# BLE_Node.net
KiCad netlist of a schematic drawn in EAGLE
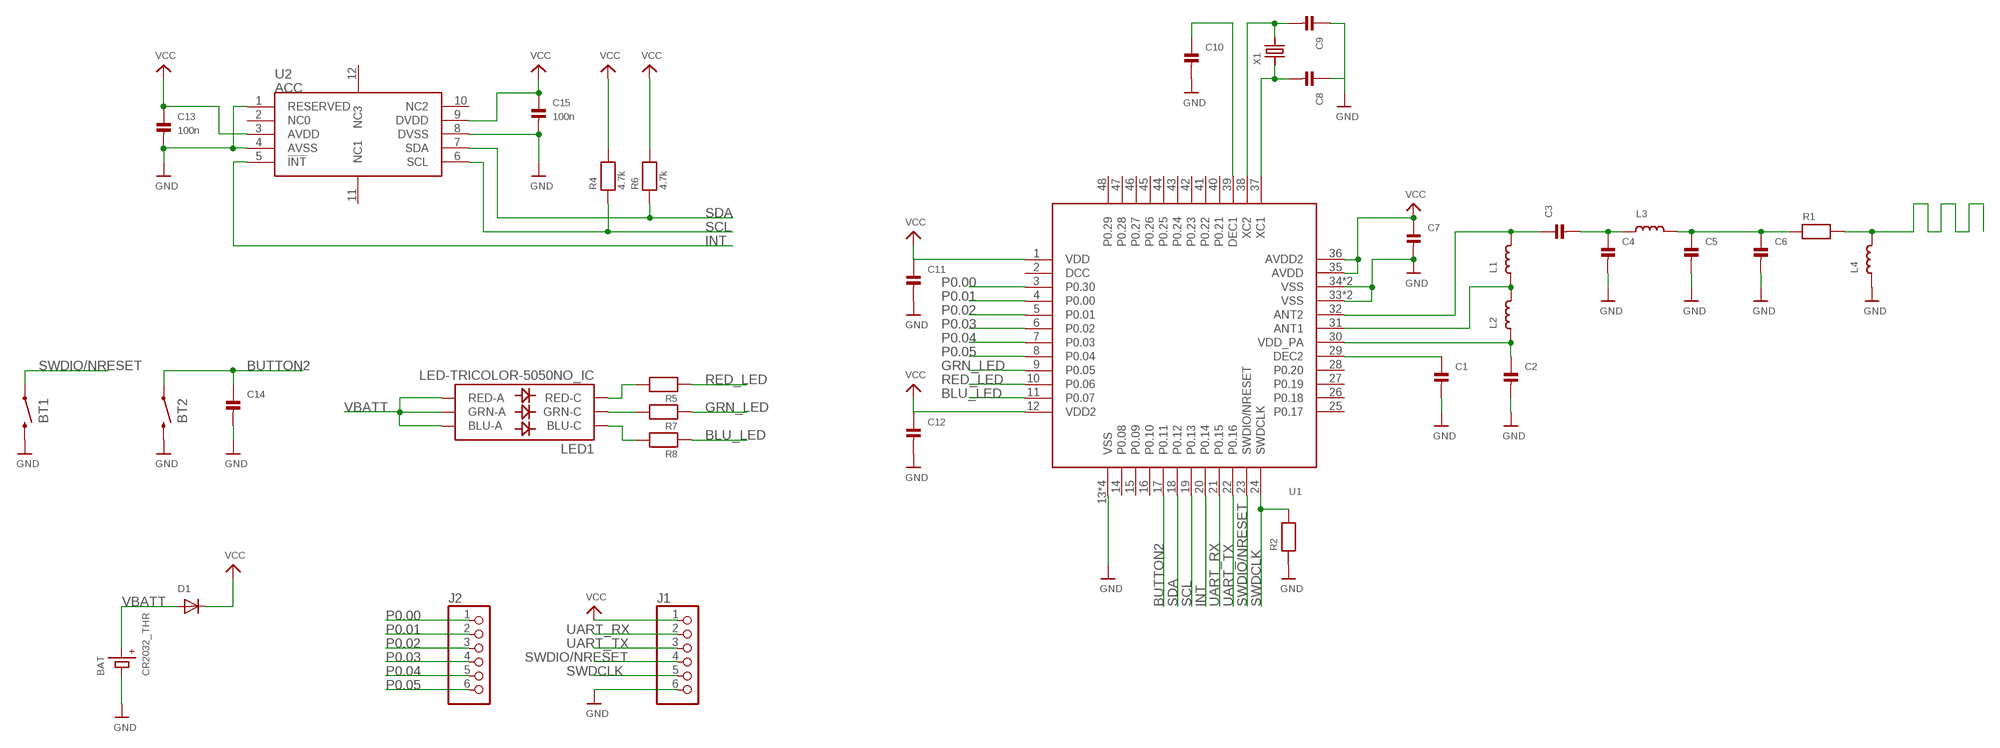
[diagram p0: schematic, sheet 1]

(export (version "E")
  (design (tool "Eeschema 10.0.6"))
  (components
    (comp (ref "BAT")
      (value "CR2032_THR")
      (footprint "eagle-import:CR2032_THR")
      (libsource (lib "eagle-import") (part "CR2032_THR"))
    )
    (comp (ref "BT1")
      (value "TACT_SWITCH_3.5MM_6MM")
      (footprint "eagle-import:TACT_SW_3.5MM_6MM")
      (libsource (lib "eagle-import") (part "TACT_SWITCH_3.5MM_6MM"))
    )
    (comp (ref "BT2")
      (value "TACT_SWITCH_3.5MM_6MM")
      (footprint "eagle-import:TACT_SW_3.5MM_6MM")
      (libsource (lib "eagle-import") (part "TACT_SWITCH_3.5MM_6MM"))
    )
    (comp (ref "C1")
      (value "NRF51_CAP_0402")
      (footprint "eagle-import:NRF51_CAP_0402")
      (libsource (lib "eagle-import") (part "NRF51_CAP_0402"))
    )
    (comp (ref "C2")
      (value "NRF51_CAP_0402")
      (footprint "eagle-import:NRF51_CAP_0402")
      (libsource (lib "eagle-import") (part "NRF51_CAP_0402"))
    )
    (comp (ref "C3")
      (value "NRF51_CAP_0402")
      (footprint "eagle-import:NRF51_CAP_0402")
      (libsource (lib "eagle-import") (part "NRF51_CAP_0402"))
    )
    (comp (ref "C4")
      (value "NRF51_CAP_0402")
      (footprint "eagle-import:NRF51_CAP_0402")
      (libsource (lib "eagle-import") (part "NRF51_CAP_0402"))
    )
    (comp (ref "C5")
      (value "NRF51_CAP_0402")
      (footprint "eagle-import:NRF51_CAP_0402")
      (libsource (lib "eagle-import") (part "NRF51_CAP_0402"))
    )
    (comp (ref "C6")
      (value "NRF51_CAP_0402")
      (footprint "eagle-import:NRF51_CAP_0402")
      (libsource (lib "eagle-import") (part "NRF51_CAP_0402"))
    )
    (comp (ref "C7")
      (value "NRF51_CAP_0402")
      (footprint "eagle-import:NRF51_CAP_0402")
      (libsource (lib "eagle-import") (part "NRF51_CAP_0402"))
    )
    (comp (ref "C8")
      (value "NRF51_CAP_0402")
      (footprint "eagle-import:NRF51_CAP_0402")
      (libsource (lib "eagle-import") (part "NRF51_CAP_0402"))
    )
    (comp (ref "C9")
      (value "NRF51_CAP_0402")
      (footprint "eagle-import:NRF51_CAP_0402")
      (libsource (lib "eagle-import") (part "NRF51_CAP_0402"))
    )
    (comp (ref "C10")
      (value "NRF51_CAP_0402")
      (footprint "eagle-import:NRF51_CAP_0402")
      (libsource (lib "eagle-import") (part "NRF51_CAP_0402"))
    )
    (comp (ref "C11")
      (value "NRF51_CAP_0402")
      (footprint "eagle-import:NRF51_CAP_0402")
      (libsource (lib "eagle-import") (part "NRF51_CAP_0402"))
    )
    (comp (ref "C12")
      (value "NRF51_CAP_0402")
      (footprint "eagle-import:NRF51_CAP_0402")
      (libsource (lib "eagle-import") (part "NRF51_CAP_0402"))
    )
    (comp (ref "C13")
      (value "100n")
      (footprint "eagle-import:NRF51_CAP_0402")
      (libsource (lib "eagle-import") (part "NRF51_CAP_0402"))
    )
    (comp (ref "C14")
      (value "NRF51_CAP_0402")
      (footprint "eagle-import:NRF51_CAP_0402")
      (libsource (lib "eagle-import") (part "NRF51_CAP_0402"))
    )
    (comp (ref "C15")
      (value "100n")
      (footprint "eagle-import:NRF51_CAP_0402")
      (libsource (lib "eagle-import") (part "NRF51_CAP_0402"))
    )
    (comp (ref "D1")
      (value "DIODESOT23_REFLOW")
      (footprint "eagle-import:SOT23-R")
      (libsource (lib "eagle-import") (part "DIODESOT23_REFLOW"))
    )
    (comp (ref "J1")
      (value "HEADER-1X6ROUND")
      (footprint "eagle-import:1X06_ROUND")
      (libsource (lib "eagle-import") (part "HEADER-1X6ROUND"))
    )
    (comp (ref "J2")
      (value "HEADER-1X6ROUND")
      (footprint "eagle-import:1X06_ROUND")
      (libsource (lib "eagle-import") (part "HEADER-1X6ROUND"))
    )
    (comp (ref "L1")
      (value "NRF51_IND_0402")
      (footprint "eagle-import:NRF51_IND_0402")
      (libsource (lib "eagle-import") (part "NRF51_IND_0402"))
    )
    (comp (ref "L2")
      (value "NRF51_IND_0402")
      (footprint "eagle-import:NRF51_IND_0402")
      (libsource (lib "eagle-import") (part "NRF51_IND_0402"))
    )
    (comp (ref "L3")
      (value "NRF51_IND_0402")
      (footprint "eagle-import:NRF51_IND_0402")
      (libsource (lib "eagle-import") (part "NRF51_IND_0402"))
    )
    (comp (ref "L4")
      (value "NRF51_IND_0402")
      (footprint "eagle-import:NRF51_IND_0402")
      (libsource (lib "eagle-import") (part "NRF51_IND_0402"))
    )
    (comp (ref "LED1")
      (value "LED-TRICOLOR-5050NO_IC")
      (footprint "eagle-import:LED-TRICOLOR-5050")
      (libsource (lib "eagle-import") (part "LED-TRICOLOR-5050NO_IC"))
    )
    (comp (ref "R1")
      (value "NRF51_RES_0402")
      (footprint "eagle-import:NRF51_RES_0402")
      (libsource (lib "eagle-import") (part "NRF51_RES_0402"))
    )
    (comp (ref "R2")
      (value "NRF51_RES_0402")
      (footprint "eagle-import:NRF51_RES_0402")
      (libsource (lib "eagle-import") (part "NRF51_RES_0402"))
    )
    (comp (ref "R4")
      (value "4.7k")
      (footprint "eagle-import:NRF51_RES_0402")
      (libsource (lib "eagle-import") (part "NRF51_RES_0402"))
    )
    (comp (ref "R5")
      (value "NRF51_RES_0402")
      (footprint "eagle-import:NRF51_RES_0402")
      (libsource (lib "eagle-import") (part "NRF51_RES_0402"))
    )
    (comp (ref "R6")
      (value "4.7k")
      (footprint "eagle-import:NRF51_RES_0402")
      (libsource (lib "eagle-import") (part "NRF51_RES_0402"))
    )
    (comp (ref "R7")
      (value "NRF51_RES_0402")
      (footprint "eagle-import:NRF51_RES_0402")
      (libsource (lib "eagle-import") (part "NRF51_RES_0402"))
    )
    (comp (ref "R8")
      (value "NRF51_RES_0402")
      (footprint "eagle-import:NRF51_RES_0402")
      (libsource (lib "eagle-import") (part "NRF51_RES_0402"))
    )
    (comp (ref "U1")
      (value "NRF51822_QFN48")
      (footprint "eagle-import:NORDIC_QFN48")
      (libsource (lib "eagle-import") (part "NRF51822_QFN48"))
    )
    (comp (ref "U2")
      (value "ACC")
      (footprint "eagle-import:DFN10")
      (libsource (lib "eagle-import") (part "MMA7660FC_DFN10"))
    )
    (comp (ref "X1")
      (value "TSX-3225_16MHZ")
      (footprint "eagle-import:XTAL_3.2X2.5")
      (libsource (lib "eagle-import") (part "TSX-3225_16MHZ"))
    )
  )
  (nets
    (net (code "1") (name "/BLU_LED") (class "Default")
      (node (ref "R8") (pin "1") (pinfunction "1_1") (pintype "passive"))
      (node (ref "U1") (pin "11") (pinfunction "P0.07_11") (pintype "bidirectional"))
    )
    (net (code "2") (name "/BUTTON2") (class "Default")
      (node (ref "BT2") (pin "1") (pinfunction "1_1") (pintype "passive"))
      (node (ref "C14") (pin "1") (pinfunction "P$1_1") (pintype "passive"))
      (node (ref "U1") (pin "17") (pinfunction "P0.11_17") (pintype "bidirectional"))
    )
    (net (code "3") (name "/GRN_LED") (class "Default")
      (node (ref "R7") (pin "1") (pinfunction "1_1") (pintype "passive"))
      (node (ref "U1") (pin "9") (pinfunction "P0.05_9") (pintype "bidirectional"))
    )
    (net (code "4") (name "/INT") (class "Default")
      (node (ref "U1") (pin "20") (pinfunction "P0.14_20") (pintype "bidirectional"))
      (node (ref "U2") (pin "5") (pinfunction "~{INT}_5") (pintype "bidirectional"))
    )
    (net (code "5") (name "/P0.00") (class "Default")
      (node (ref "J2") (pin "1") (pinfunction "1_1") (pintype "passive"))
      (node (ref "U1") (pin "3") (pinfunction "P0.30_3") (pintype "bidirectional"))
    )
    (net (code "6") (name "/P0.01") (class "Default")
      (node (ref "J2") (pin "2") (pinfunction "2_2") (pintype "passive"))
      (node (ref "U1") (pin "4") (pinfunction "P0.00_4") (pintype "bidirectional"))
    )
    (net (code "7") (name "/P0.02") (class "Default")
      (node (ref "J2") (pin "3") (pinfunction "3_3") (pintype "passive"))
      (node (ref "U1") (pin "5") (pinfunction "P0.01_5") (pintype "bidirectional"))
    )
    (net (code "8") (name "/P0.03") (class "Default")
      (node (ref "J2") (pin "4") (pinfunction "4_4") (pintype "passive"))
      (node (ref "U1") (pin "6") (pinfunction "P0.02_6") (pintype "bidirectional"))
    )
    (net (code "9") (name "/P0.04") (class "Default")
      (node (ref "J2") (pin "5") (pinfunction "5_5") (pintype "passive"))
      (node (ref "U1") (pin "7") (pinfunction "P0.03_7") (pintype "bidirectional"))
    )
    (net (code "10") (name "/P0.05") (class "Default")
      (node (ref "J2") (pin "6") (pinfunction "6_6") (pintype "passive"))
      (node (ref "U1") (pin "8") (pinfunction "P0.04_8") (pintype "bidirectional"))
    )
    (net (code "11") (name "/RED_LED") (class "Default")
      (node (ref "R5") (pin "1") (pinfunction "1_1") (pintype "passive"))
      (node (ref "U1") (pin "10") (pinfunction "P0.06_10") (pintype "bidirectional"))
    )
    (net (code "12") (name "/SCL") (class "Default")
      (node (ref "R4") (pin "1") (pinfunction "1_1") (pintype "passive"))
      (node (ref "U1") (pin "19") (pinfunction "P0.13_19") (pintype "bidirectional"))
      (node (ref "U2") (pin "6") (pinfunction "SCL_6") (pintype "bidirectional"))
    )
    (net (code "13") (name "/SDA") (class "Default")
      (node (ref "R6") (pin "1") (pinfunction "1_1") (pintype "passive"))
      (node (ref "U1") (pin "18") (pinfunction "P0.12_18") (pintype "bidirectional"))
      (node (ref "U2") (pin "7") (pinfunction "SDA_7") (pintype "bidirectional"))
    )
    (net (code "14") (name "/SWDCLK") (class "Default")
      (node (ref "J1") (pin "5") (pinfunction "5_5") (pintype "passive"))
      (node (ref "R2") (pin "2") (pinfunction "2_2") (pintype "passive"))
      (node (ref "U1") (pin "24") (pinfunction "SWDCLK_24") (pintype "bidirectional"))
    )
    (net (code "15") (name "/SWDIO{slash}NRESET") (class "Default")
      (node (ref "BT1") (pin "1") (pinfunction "1_1") (pintype "passive"))
      (node (ref "J1") (pin "4") (pinfunction "4_4") (pintype "passive"))
      (node (ref "U1") (pin "23") (pinfunction "SWDIO/NRESET_23") (pintype "bidirectional"))
    )
    (net (code "16") (name "/UART_RX") (class "Default")
      (node (ref "J1") (pin "2") (pinfunction "2_2") (pintype "passive"))
      (node (ref "U1") (pin "21") (pinfunction "P0.15_21") (pintype "bidirectional"))
    )
    (net (code "17") (name "/UART_TX") (class "Default")
      (node (ref "J1") (pin "3") (pinfunction "3_3") (pintype "passive"))
      (node (ref "U1") (pin "22") (pinfunction "P0.16_22") (pintype "bidirectional"))
    )
    (net (code "18") (name "/VBATT") (class "Default")
      (node (ref "BAT") (pin "1") (pinfunction "+_1") (pintype "power_in"))
      (node (ref "BAT") (pin "2") (pinfunction "+_2") (pintype "power_in"))
      (node (ref "BAT") (pin "3") (pinfunction "+_3") (pintype "power_in"))
      (node (ref "BAT") (pin "4") (pinfunction "+_4") (pintype "power_in"))
      (node (ref "D1") (pin "1") (pinfunction "A_1") (pintype "passive"))
      (node (ref "LED1") (pin "1") (pinfunction "GRN-A_1") (pintype "bidirectional"))
      (node (ref "LED1") (pin "2") (pinfunction "RED-A_2") (pintype "bidirectional"))
      (node (ref "LED1") (pin "3") (pinfunction "BLU-A_3") (pintype "bidirectional"))
    )
    (net (code "19") (name "GND") (class "Default")
      (node (ref "BAT") (pin "5") (pinfunction "-_5") (pintype "power_in"))
      (node (ref "BT1") (pin "2") (pinfunction "2_2") (pintype "passive"))
      (node (ref "BT2") (pin "2") (pinfunction "2_2") (pintype "passive"))
      (node (ref "C1") (pin "2") (pinfunction "P$2_2") (pintype "passive"))
      (node (ref "C10") (pin "2") (pinfunction "P$2_2") (pintype "passive"))
      (node (ref "C11") (pin "2") (pinfunction "P$2_2") (pintype "passive"))
      (node (ref "C12") (pin "2") (pinfunction "P$2_2") (pintype "passive"))
      (node (ref "C13") (pin "2") (pinfunction "P$2_2") (pintype "passive"))
      (node (ref "C14") (pin "2") (pinfunction "P$2_2") (pintype "passive"))
      (node (ref "C15") (pin "2") (pinfunction "P$2_2") (pintype "passive"))
      (node (ref "C2") (pin "2") (pinfunction "P$2_2") (pintype "passive"))
      (node (ref "C4") (pin "2") (pinfunction "P$2_2") (pintype "passive"))
      (node (ref "C5") (pin "2") (pinfunction "P$2_2") (pintype "passive"))
      (node (ref "C6") (pin "2") (pinfunction "P$2_2") (pintype "passive"))
      (node (ref "C7") (pin "2") (pinfunction "P$2_2") (pintype "passive"))
      (node (ref "C8") (pin "1") (pinfunction "P$1_1") (pintype "passive"))
      (node (ref "C9") (pin "1") (pinfunction "P$1_1") (pintype "passive"))
      (node (ref "J1") (pin "6") (pinfunction "6_6") (pintype "passive"))
      (node (ref "L4") (pin "1") (pinfunction "1_1") (pintype "passive"))
      (node (ref "R2") (pin "1") (pinfunction "1_1") (pintype "passive"))
      (node (ref "U1") (pin "13") (pinfunction "VSS_13") (pintype "bidirectional"))
      (node (ref "U1") (pin "33") (pinfunction "VSS_33") (pintype "bidirectional"))
      (node (ref "U1") (pin "34") (pinfunction "VSS_34") (pintype "bidirectional"))
      (node (ref "U1") (pin "49") (pinfunction "VSS_49") (pintype "bidirectional"))
      (node (ref "U1") (pin "50") (pinfunction "VSS_50") (pintype "bidirectional"))
      (node (ref "U1") (pin "51") (pinfunction "VSS_51") (pintype "bidirectional"))
      (node (ref "U1") (pin "52") (pinfunction "VSS_52") (pintype "bidirectional"))
      (node (ref "U1") (pin "53") (pinfunction "VSS_53") (pintype "bidirectional"))
      (node (ref "U2") (pin "1") (pinfunction "RESERVED_1") (pintype "bidirectional"))
      (node (ref "U2") (pin "4") (pinfunction "AVSS_4") (pintype "bidirectional"))
      (node (ref "U2") (pin "8") (pinfunction "DVSS_8") (pintype "bidirectional"))
    )
    (net (code "20") (name "Net-(C1-P$1)") (class "Default")
      (node (ref "C1") (pin "1") (pinfunction "P$1_1") (pintype "passive"))
      (node (ref "U1") (pin "29") (pinfunction "DEC2_29") (pintype "bidirectional"))
    )
    (net (code "21") (name "Net-(C2-P$1)") (class "Default")
      (node (ref "C2") (pin "1") (pinfunction "P$1_1") (pintype "passive"))
      (node (ref "L2") (pin "1") (pinfunction "1_1") (pintype "passive"))
      (node (ref "U1") (pin "30") (pinfunction "VDD_PA_30") (pintype "bidirectional"))
    )
    (net (code "22") (name "Net-(C3-P$1)") (class "Default")
      (node (ref "C3") (pin "1") (pinfunction "P$1_1") (pintype "passive"))
      (node (ref "L1") (pin "2") (pinfunction "2_2") (pintype "passive"))
      (node (ref "U1") (pin "32") (pinfunction "ANT2_32") (pintype "bidirectional"))
    )
    (net (code "23") (name "Net-(C3-P$2)") (class "Default")
      (node (ref "C3") (pin "2") (pinfunction "P$2_2") (pintype "passive"))
      (node (ref "C4") (pin "1") (pinfunction "P$1_1") (pintype "passive"))
      (node (ref "L3") (pin "1") (pinfunction "1_1") (pintype "passive"))
    )
    (net (code "24") (name "Net-(C5-P$1)") (class "Default")
      (node (ref "C5") (pin "1") (pinfunction "P$1_1") (pintype "passive"))
      (node (ref "C6") (pin "1") (pinfunction "P$1_1") (pintype "passive"))
      (node (ref "L3") (pin "2") (pinfunction "2_2") (pintype "passive"))
      (node (ref "R1") (pin "1") (pinfunction "1_1") (pintype "passive"))
    )
    (net (code "25") (name "Net-(C8-P$2)") (class "Default")
      (node (ref "C8") (pin "2") (pinfunction "P$2_2") (pintype "passive"))
      (node (ref "U1") (pin "37") (pinfunction "XC1_37") (pintype "bidirectional"))
      (node (ref "X1") (pin "1") (pinfunction "1_1") (pintype "passive"))
    )
    (net (code "26") (name "Net-(C9-P$2)") (class "Default")
      (node (ref "C9") (pin "2") (pinfunction "P$2_2") (pintype "passive"))
      (node (ref "U1") (pin "38") (pinfunction "XC2_38") (pintype "bidirectional"))
      (node (ref "X1") (pin "3") (pinfunction "2_3") (pintype "passive"))
    )
    (net (code "27") (name "Net-(C10-P$1)") (class "Default")
      (node (ref "C10") (pin "1") (pinfunction "P$1_1") (pintype "passive"))
      (node (ref "U1") (pin "39") (pinfunction "DEC1_39") (pintype "bidirectional"))
    )
    (net (code "28") (name "Net-(L4-Pad2)") (class "Default")
      (node (ref "L4") (pin "2") (pinfunction "2_2") (pintype "passive"))
      (node (ref "R1") (pin "2") (pinfunction "2_2") (pintype "passive"))
    )
    (net (code "29") (name "Net-(LED1-BLU-C)") (class "Default")
      (node (ref "LED1") (pin "4") (pinfunction "BLU-C_4") (pintype "bidirectional"))
      (node (ref "R8") (pin "2") (pinfunction "2_2") (pintype "passive"))
    )
    (net (code "30") (name "Net-(LED1-GRN-C)") (class "Default")
      (node (ref "LED1") (pin "6") (pinfunction "GRN-C_6") (pintype "bidirectional"))
      (node (ref "R7") (pin "2") (pinfunction "2_2") (pintype "passive"))
    )
    (net (code "31") (name "Net-(LED1-RED-C)") (class "Default")
      (node (ref "LED1") (pin "5") (pinfunction "RED-C_5") (pintype "bidirectional"))
      (node (ref "R5") (pin "2") (pinfunction "2_2") (pintype "passive"))
    )
    (net (code "32") (name "Net-(U1-ANT1)") (class "Default")
      (node (ref "L1") (pin "1") (pinfunction "1_1") (pintype "passive"))
      (node (ref "L2") (pin "2") (pinfunction "2_2") (pintype "passive"))
      (node (ref "U1") (pin "31") (pinfunction "ANT1_31") (pintype "bidirectional"))
    )
    (net (code "33") (name "VCC") (class "Default")
      (node (ref "C11") (pin "1") (pinfunction "P$1_1") (pintype "passive"))
      (node (ref "C12") (pin "1") (pinfunction "P$1_1") (pintype "passive"))
      (node (ref "C13") (pin "1") (pinfunction "P$1_1") (pintype "passive"))
      (node (ref "C15") (pin "1") (pinfunction "P$1_1") (pintype "passive"))
      (node (ref "C7") (pin "1") (pinfunction "P$1_1") (pintype "passive"))
      (node (ref "D1") (pin "3") (pinfunction "C_3") (pintype "passive"))
      (node (ref "J1") (pin "1") (pinfunction "1_1") (pintype "passive"))
      (node (ref "R4") (pin "2") (pinfunction "2_2") (pintype "passive"))
      (node (ref "R6") (pin "2") (pinfunction "2_2") (pintype "passive"))
      (node (ref "U1") (pin "1") (pinfunction "VDD_1") (pintype "bidirectional"))
      (node (ref "U1") (pin "12") (pinfunction "VDD2_12") (pintype "bidirectional"))
      (node (ref "U1") (pin "35") (pinfunction "AVDD_35") (pintype "bidirectional"))
      (node (ref "U1") (pin "36") (pinfunction "AVDD2_36") (pintype "bidirectional"))
      (node (ref "U2") (pin "3") (pinfunction "AVDD_3") (pintype "bidirectional"))
      (node (ref "U2") (pin "9") (pinfunction "DVDD_9") (pintype "bidirectional"))
    )
    (net (code "34") (name "unconnected-(U1-DCC-Pad2)") (class "Default")
      (node (ref "U1") (pin "2") (pinfunction "DCC_2") (pintype "bidirectional"))
    )
    (net (code "35") (name "unconnected-(U1-P0.08-Pad14)") (class "Default")
      (node (ref "U1") (pin "14") (pinfunction "P0.08_14") (pintype "bidirectional"))
    )
    (net (code "36") (name "unconnected-(U1-P0.09-Pad15)") (class "Default")
      (node (ref "U1") (pin "15") (pinfunction "P0.09_15") (pintype "bidirectional"))
    )
    (net (code "37") (name "unconnected-(U1-P0.10-Pad16)") (class "Default")
      (node (ref "U1") (pin "16") (pinfunction "P0.10_16") (pintype "bidirectional"))
    )
    (net (code "38") (name "unconnected-(U1-P0.17-Pad25)") (class "Default")
      (node (ref "U1") (pin "25") (pinfunction "P0.17_25") (pintype "bidirectional"))
    )
    (net (code "39") (name "unconnected-(U1-P0.18-Pad26)") (class "Default")
      (node (ref "U1") (pin "26") (pinfunction "P0.18_26") (pintype "bidirectional"))
    )
    (net (code "40") (name "unconnected-(U1-P0.19-Pad27)") (class "Default")
      (node (ref "U1") (pin "27") (pinfunction "P0.19_27") (pintype "bidirectional"))
    )
    (net (code "41") (name "unconnected-(U1-P0.20-Pad28)") (class "Default")
      (node (ref "U1") (pin "28") (pinfunction "P0.20_28") (pintype "bidirectional"))
    )
    (net (code "42") (name "unconnected-(U1-P0.21-Pad40)") (class "Default")
      (node (ref "U1") (pin "40") (pinfunction "P0.21_40") (pintype "bidirectional"))
    )
    (net (code "43") (name "unconnected-(U1-P0.22-Pad41)") (class "Default")
      (node (ref "U1") (pin "41") (pinfunction "P0.22_41") (pintype "bidirectional"))
    )
    (net (code "44") (name "unconnected-(U1-P0.23-Pad42)") (class "Default")
      (node (ref "U1") (pin "42") (pinfunction "P0.23_42") (pintype "bidirectional"))
    )
    (net (code "45") (name "unconnected-(U1-P0.24-Pad43)") (class "Default")
      (node (ref "U1") (pin "43") (pinfunction "P0.24_43") (pintype "bidirectional"))
    )
    (net (code "46") (name "unconnected-(U1-P0.25-Pad44)") (class "Default")
      (node (ref "U1") (pin "44") (pinfunction "P0.25_44") (pintype "bidirectional"))
    )
    (net (code "47") (name "unconnected-(U1-P0.26-Pad45)") (class "Default")
      (node (ref "U1") (pin "45") (pinfunction "P0.26_45") (pintype "bidirectional"))
    )
    (net (code "48") (name "unconnected-(U1-P0.27-Pad46)") (class "Default")
      (node (ref "U1") (pin "46") (pinfunction "P0.27_46") (pintype "bidirectional"))
    )
    (net (code "49") (name "unconnected-(U1-P0.28-Pad47)") (class "Default")
      (node (ref "U1") (pin "47") (pinfunction "P0.28_47") (pintype "bidirectional"))
    )
    (net (code "50") (name "unconnected-(U1-P0.29-Pad48)") (class "Default")
      (node (ref "U1") (pin "48") (pinfunction "P0.29_48") (pintype "bidirectional"))
    )
    (net (code "51") (name "unconnected-(U2-NC0-Pad2)") (class "Default")
      (node (ref "U2") (pin "2") (pinfunction "NC0_2") (pintype "bidirectional"))
    )
    (net (code "52") (name "unconnected-(U2-NC1-Pad11)") (class "Default")
      (node (ref "U2") (pin "11") (pinfunction "NC1_11") (pintype "bidirectional"))
    )
    (net (code "53") (name "unconnected-(U2-NC2-Pad10)") (class "Default")
      (node (ref "U2") (pin "10") (pinfunction "NC2_10") (pintype "bidirectional"))
    )
    (net (code "54") (name "unconnected-(U2-NC3-Pad12)") (class "Default")
      (node (ref "U2") (pin "12") (pinfunction "NC3_12") (pintype "bidirectional"))
    )
  )
)
